# Decoup_Cap_2.net
KiCad netlist of a schematic drawn in Altium Designer
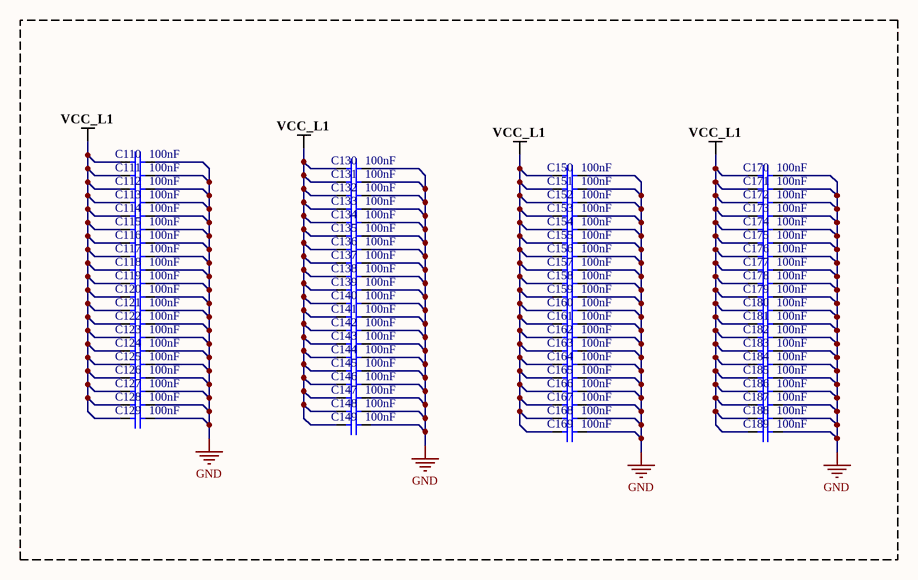
[diagram p0: Decoup_Cap 2.SchDoc]

(export (version "E")
  (design (tool "Eeschema 10.0.6"))
  (components
    (comp (ref "C110")
      (value "100nF")
      (footprint "Cap0402")
      (description "CAP CER 0.1UF 25V X7R 0402")
      (fields
        (field (name "MANUFACTURER") "Yageo")
        (field (name "MANUFACTURER PART NUMBER") "CC0402KRX7R8BB104")
      )
      (libsource (lib "TT_IntLib") (part "CC0402KRX7R8BB104"))
    )
    (comp (ref "C111")
      (value "100nF")
      (footprint "Cap0402")
      (description "CAP CER 0.1UF 25V X7R 0402")
      (fields
        (field (name "MANUFACTURER") "Yageo")
        (field (name "MANUFACTURER PART NUMBER") "CC0402KRX7R8BB104")
      )
      (libsource (lib "TT_IntLib") (part "CC0402KRX7R8BB104"))
    )
    (comp (ref "C112")
      (value "100nF")
      (footprint "Cap0402")
      (description "CAP CER 0.1UF 25V X7R 0402")
      (fields
        (field (name "MANUFACTURER") "Yageo")
        (field (name "MANUFACTURER PART NUMBER") "CC0402KRX7R8BB104")
      )
      (libsource (lib "TT_IntLib") (part "CC0402KRX7R8BB104"))
    )
    (comp (ref "C113")
      (value "100nF")
      (footprint "Cap0402")
      (description "CAP CER 0.1UF 25V X7R 0402")
      (fields
        (field (name "MANUFACTURER") "Yageo")
        (field (name "MANUFACTURER PART NUMBER") "CC0402KRX7R8BB104")
      )
      (libsource (lib "TT_IntLib") (part "CC0402KRX7R8BB104"))
    )
    (comp (ref "C114")
      (value "100nF")
      (footprint "Cap0402")
      (description "CAP CER 0.1UF 25V X7R 0402")
      (fields
        (field (name "MANUFACTURER") "Yageo")
        (field (name "MANUFACTURER PART NUMBER") "CC0402KRX7R8BB104")
      )
      (libsource (lib "TT_IntLib") (part "CC0402KRX7R8BB104"))
    )
    (comp (ref "C115")
      (value "100nF")
      (footprint "Cap0402")
      (description "CAP CER 0.1UF 25V X7R 0402")
      (fields
        (field (name "MANUFACTURER") "Yageo")
        (field (name "MANUFACTURER PART NUMBER") "CC0402KRX7R8BB104")
      )
      (libsource (lib "TT_IntLib") (part "CC0402KRX7R8BB104"))
    )
    (comp (ref "C116")
      (value "100nF")
      (footprint "Cap0402")
      (description "CAP CER 0.1UF 25V X7R 0402")
      (fields
        (field (name "MANUFACTURER") "Yageo")
        (field (name "MANUFACTURER PART NUMBER") "CC0402KRX7R8BB104")
      )
      (libsource (lib "TT_IntLib") (part "CC0402KRX7R8BB104"))
    )
    (comp (ref "C117")
      (value "100nF")
      (footprint "Cap0402")
      (description "CAP CER 0.1UF 25V X7R 0402")
      (fields
        (field (name "MANUFACTURER") "Yageo")
        (field (name "MANUFACTURER PART NUMBER") "CC0402KRX7R8BB104")
      )
      (libsource (lib "TT_IntLib") (part "CC0402KRX7R8BB104"))
    )
    (comp (ref "C118")
      (value "100nF")
      (footprint "Cap0402")
      (description "CAP CER 0.1UF 25V X7R 0402")
      (fields
        (field (name "MANUFACTURER") "Yageo")
        (field (name "MANUFACTURER PART NUMBER") "CC0402KRX7R8BB104")
      )
      (libsource (lib "TT_IntLib") (part "CC0402KRX7R8BB104"))
    )
    (comp (ref "C119")
      (value "100nF")
      (footprint "Cap0402")
      (description "CAP CER 0.1UF 25V X7R 0402")
      (fields
        (field (name "MANUFACTURER") "Yageo")
        (field (name "MANUFACTURER PART NUMBER") "CC0402KRX7R8BB104")
      )
      (libsource (lib "TT_IntLib") (part "CC0402KRX7R8BB104"))
    )
    (comp (ref "C120")
      (value "100nF")
      (footprint "Cap0402")
      (description "CAP CER 0.1UF 25V X7R 0402")
      (fields
        (field (name "MANUFACTURER") "Yageo")
        (field (name "MANUFACTURER PART NUMBER") "CC0402KRX7R8BB104")
      )
      (libsource (lib "TT_IntLib") (part "CC0402KRX7R8BB104"))
    )
    (comp (ref "C121")
      (value "100nF")
      (footprint "Cap0402")
      (description "CAP CER 0.1UF 25V X7R 0402")
      (fields
        (field (name "MANUFACTURER") "Yageo")
        (field (name "MANUFACTURER PART NUMBER") "CC0402KRX7R8BB104")
      )
      (libsource (lib "TT_IntLib") (part "CC0402KRX7R8BB104"))
    )
    (comp (ref "C122")
      (value "100nF")
      (footprint "Cap0402")
      (description "CAP CER 0.1UF 25V X7R 0402")
      (fields
        (field (name "MANUFACTURER") "Yageo")
        (field (name "MANUFACTURER PART NUMBER") "CC0402KRX7R8BB104")
      )
      (libsource (lib "TT_IntLib") (part "CC0402KRX7R8BB104"))
    )
    (comp (ref "C123")
      (value "100nF")
      (footprint "Cap0402")
      (description "CAP CER 0.1UF 25V X7R 0402")
      (fields
        (field (name "MANUFACTURER") "Yageo")
        (field (name "MANUFACTURER PART NUMBER") "CC0402KRX7R8BB104")
      )
      (libsource (lib "TT_IntLib") (part "CC0402KRX7R8BB104"))
    )
    (comp (ref "C124")
      (value "100nF")
      (footprint "Cap0402")
      (description "CAP CER 0.1UF 25V X7R 0402")
      (fields
        (field (name "MANUFACTURER") "Yageo")
        (field (name "MANUFACTURER PART NUMBER") "CC0402KRX7R8BB104")
      )
      (libsource (lib "TT_IntLib") (part "CC0402KRX7R8BB104"))
    )
    (comp (ref "C125")
      (value "100nF")
      (footprint "Cap0402")
      (description "CAP CER 0.1UF 25V X7R 0402")
      (fields
        (field (name "MANUFACTURER") "Yageo")
        (field (name "MANUFACTURER PART NUMBER") "CC0402KRX7R8BB104")
      )
      (libsource (lib "TT_IntLib") (part "CC0402KRX7R8BB104"))
    )
    (comp (ref "C126")
      (value "100nF")
      (footprint "Cap0402")
      (description "CAP CER 0.1UF 25V X7R 0402")
      (fields
        (field (name "MANUFACTURER") "Yageo")
        (field (name "MANUFACTURER PART NUMBER") "CC0402KRX7R8BB104")
      )
      (libsource (lib "TT_IntLib") (part "CC0402KRX7R8BB104"))
    )
    (comp (ref "C127")
      (value "100nF")
      (footprint "Cap0402")
      (description "CAP CER 0.1UF 25V X7R 0402")
      (fields
        (field (name "MANUFACTURER") "Yageo")
        (field (name "MANUFACTURER PART NUMBER") "CC0402KRX7R8BB104")
      )
      (libsource (lib "TT_IntLib") (part "CC0402KRX7R8BB104"))
    )
    (comp (ref "C128")
      (value "100nF")
      (footprint "Cap0402")
      (description "CAP CER 0.1UF 25V X7R 0402")
      (fields
        (field (name "MANUFACTURER") "Yageo")
        (field (name "MANUFACTURER PART NUMBER") "CC0402KRX7R8BB104")
      )
      (libsource (lib "TT_IntLib") (part "CC0402KRX7R8BB104"))
    )
    (comp (ref "C129")
      (value "100nF")
      (footprint "Cap0402")
      (description "CAP CER 0.1UF 25V X7R 0402")
      (fields
        (field (name "MANUFACTURER") "Yageo")
        (field (name "MANUFACTURER PART NUMBER") "CC0402KRX7R8BB104")
      )
      (libsource (lib "TT_IntLib") (part "CC0402KRX7R8BB104"))
    )
    (comp (ref "C130")
      (value "100nF")
      (footprint "Cap0402")
      (description "CAP CER 0.1UF 25V X7R 0402")
      (fields
        (field (name "MANUFACTURER") "Yageo")
        (field (name "MANUFACTURER PART NUMBER") "CC0402KRX7R8BB104")
      )
      (libsource (lib "TT_IntLib") (part "CC0402KRX7R8BB104"))
    )
    (comp (ref "C131")
      (value "100nF")
      (footprint "Cap0402")
      (description "CAP CER 0.1UF 25V X7R 0402")
      (fields
        (field (name "MANUFACTURER") "Yageo")
        (field (name "MANUFACTURER PART NUMBER") "CC0402KRX7R8BB104")
      )
      (libsource (lib "TT_IntLib") (part "CC0402KRX7R8BB104"))
    )
    (comp (ref "C132")
      (value "100nF")
      (footprint "Cap0402")
      (description "CAP CER 0.1UF 25V X7R 0402")
      (fields
        (field (name "MANUFACTURER") "Yageo")
        (field (name "MANUFACTURER PART NUMBER") "CC0402KRX7R8BB104")
      )
      (libsource (lib "TT_IntLib") (part "CC0402KRX7R8BB104"))
    )
    (comp (ref "C133")
      (value "100nF")
      (footprint "Cap0402")
      (description "CAP CER 0.1UF 25V X7R 0402")
      (fields
        (field (name "MANUFACTURER") "Yageo")
        (field (name "MANUFACTURER PART NUMBER") "CC0402KRX7R8BB104")
      )
      (libsource (lib "TT_IntLib") (part "CC0402KRX7R8BB104"))
    )
    (comp (ref "C134")
      (value "100nF")
      (footprint "Cap0402")
      (description "CAP CER 0.1UF 25V X7R 0402")
      (fields
        (field (name "MANUFACTURER") "Yageo")
        (field (name "MANUFACTURER PART NUMBER") "CC0402KRX7R8BB104")
      )
      (libsource (lib "TT_IntLib") (part "CC0402KRX7R8BB104"))
    )
    (comp (ref "C135")
      (value "100nF")
      (footprint "Cap0402")
      (description "CAP CER 0.1UF 25V X7R 0402")
      (fields
        (field (name "MANUFACTURER") "Yageo")
        (field (name "MANUFACTURER PART NUMBER") "CC0402KRX7R8BB104")
      )
      (libsource (lib "TT_IntLib") (part "CC0402KRX7R8BB104"))
    )
    (comp (ref "C136")
      (value "100nF")
      (footprint "Cap0402")
      (description "CAP CER 0.1UF 25V X7R 0402")
      (fields
        (field (name "MANUFACTURER") "Yageo")
        (field (name "MANUFACTURER PART NUMBER") "CC0402KRX7R8BB104")
      )
      (libsource (lib "TT_IntLib") (part "CC0402KRX7R8BB104"))
    )
    (comp (ref "C137")
      (value "100nF")
      (footprint "Cap0402")
      (description "CAP CER 0.1UF 25V X7R 0402")
      (fields
        (field (name "MANUFACTURER") "Yageo")
        (field (name "MANUFACTURER PART NUMBER") "CC0402KRX7R8BB104")
      )
      (libsource (lib "TT_IntLib") (part "CC0402KRX7R8BB104"))
    )
    (comp (ref "C138")
      (value "100nF")
      (footprint "Cap0402")
      (description "CAP CER 0.1UF 25V X7R 0402")
      (fields
        (field (name "MANUFACTURER") "Yageo")
        (field (name "MANUFACTURER PART NUMBER") "CC0402KRX7R8BB104")
      )
      (libsource (lib "TT_IntLib") (part "CC0402KRX7R8BB104"))
    )
    (comp (ref "C139")
      (value "100nF")
      (footprint "Cap0402")
      (description "CAP CER 0.1UF 25V X7R 0402")
      (fields
        (field (name "MANUFACTURER") "Yageo")
        (field (name "MANUFACTURER PART NUMBER") "CC0402KRX7R8BB104")
      )
      (libsource (lib "TT_IntLib") (part "CC0402KRX7R8BB104"))
    )
    (comp (ref "C140")
      (value "100nF")
      (footprint "Cap0402")
      (description "CAP CER 0.1UF 25V X7R 0402")
      (fields
        (field (name "MANUFACTURER") "Yageo")
        (field (name "MANUFACTURER PART NUMBER") "CC0402KRX7R8BB104")
      )
      (libsource (lib "TT_IntLib") (part "CC0402KRX7R8BB104"))
    )
    (comp (ref "C141")
      (value "100nF")
      (footprint "Cap0402")
      (description "CAP CER 0.1UF 25V X7R 0402")
      (fields
        (field (name "MANUFACTURER") "Yageo")
        (field (name "MANUFACTURER PART NUMBER") "CC0402KRX7R8BB104")
      )
      (libsource (lib "TT_IntLib") (part "CC0402KRX7R8BB104"))
    )
    (comp (ref "C142")
      (value "100nF")
      (footprint "Cap0402")
      (description "CAP CER 0.1UF 25V X7R 0402")
      (fields
        (field (name "MANUFACTURER") "Yageo")
        (field (name "MANUFACTURER PART NUMBER") "CC0402KRX7R8BB104")
      )
      (libsource (lib "TT_IntLib") (part "CC0402KRX7R8BB104"))
    )
    (comp (ref "C143")
      (value "100nF")
      (footprint "Cap0402")
      (description "CAP CER 0.1UF 25V X7R 0402")
      (fields
        (field (name "MANUFACTURER") "Yageo")
        (field (name "MANUFACTURER PART NUMBER") "CC0402KRX7R8BB104")
      )
      (libsource (lib "TT_IntLib") (part "CC0402KRX7R8BB104"))
    )
    (comp (ref "C144")
      (value "100nF")
      (footprint "Cap0402")
      (description "CAP CER 0.1UF 25V X7R 0402")
      (fields
        (field (name "MANUFACTURER") "Yageo")
        (field (name "MANUFACTURER PART NUMBER") "CC0402KRX7R8BB104")
      )
      (libsource (lib "TT_IntLib") (part "CC0402KRX7R8BB104"))
    )
    (comp (ref "C145")
      (value "100nF")
      (footprint "Cap0402")
      (description "CAP CER 0.1UF 25V X7R 0402")
      (fields
        (field (name "MANUFACTURER") "Yageo")
        (field (name "MANUFACTURER PART NUMBER") "CC0402KRX7R8BB104")
      )
      (libsource (lib "TT_IntLib") (part "CC0402KRX7R8BB104"))
    )
    (comp (ref "C146")
      (value "100nF")
      (footprint "Cap0402")
      (description "CAP CER 0.1UF 25V X7R 0402")
      (fields
        (field (name "MANUFACTURER") "Yageo")
        (field (name "MANUFACTURER PART NUMBER") "CC0402KRX7R8BB104")
      )
      (libsource (lib "TT_IntLib") (part "CC0402KRX7R8BB104"))
    )
    (comp (ref "C147")
      (value "100nF")
      (footprint "Cap0402")
      (description "CAP CER 0.1UF 25V X7R 0402")
      (fields
        (field (name "MANUFACTURER") "Yageo")
        (field (name "MANUFACTURER PART NUMBER") "CC0402KRX7R8BB104")
      )
      (libsource (lib "TT_IntLib") (part "CC0402KRX7R8BB104"))
    )
    (comp (ref "C148")
      (value "100nF")
      (footprint "Cap0402")
      (description "CAP CER 0.1UF 25V X7R 0402")
      (fields
        (field (name "MANUFACTURER") "Yageo")
        (field (name "MANUFACTURER PART NUMBER") "CC0402KRX7R8BB104")
      )
      (libsource (lib "TT_IntLib") (part "CC0402KRX7R8BB104"))
    )
    (comp (ref "C149")
      (value "100nF")
      (footprint "Cap0402")
      (description "CAP CER 0.1UF 25V X7R 0402")
      (fields
        (field (name "MANUFACTURER") "Yageo")
        (field (name "MANUFACTURER PART NUMBER") "CC0402KRX7R8BB104")
      )
      (libsource (lib "TT_IntLib") (part "CC0402KRX7R8BB104"))
    )
    (comp (ref "C150")
      (value "100nF")
      (footprint "Cap0402")
      (description "CAP CER 0.1UF 25V X7R 0402")
      (fields
        (field (name "MANUFACTURER") "Yageo")
        (field (name "MANUFACTURER PART NUMBER") "CC0402KRX7R8BB104")
      )
      (libsource (lib "TT_IntLib") (part "CC0402KRX7R8BB104"))
    )
    (comp (ref "C151")
      (value "100nF")
      (footprint "Cap0402")
      (description "CAP CER 0.1UF 25V X7R 0402")
      (fields
        (field (name "MANUFACTURER") "Yageo")
        (field (name "MANUFACTURER PART NUMBER") "CC0402KRX7R8BB104")
      )
      (libsource (lib "TT_IntLib") (part "CC0402KRX7R8BB104"))
    )
    (comp (ref "C152")
      (value "100nF")
      (footprint "Cap0402")
      (description "CAP CER 0.1UF 25V X7R 0402")
      (fields
        (field (name "MANUFACTURER") "Yageo")
        (field (name "MANUFACTURER PART NUMBER") "CC0402KRX7R8BB104")
      )
      (libsource (lib "TT_IntLib") (part "CC0402KRX7R8BB104"))
    )
    (comp (ref "C153")
      (value "100nF")
      (footprint "Cap0402")
      (description "CAP CER 0.1UF 25V X7R 0402")
      (fields
        (field (name "MANUFACTURER") "Yageo")
        (field (name "MANUFACTURER PART NUMBER") "CC0402KRX7R8BB104")
      )
      (libsource (lib "TT_IntLib") (part "CC0402KRX7R8BB104"))
    )
    (comp (ref "C154")
      (value "100nF")
      (footprint "Cap0402")
      (description "CAP CER 0.1UF 25V X7R 0402")
      (fields
        (field (name "MANUFACTURER") "Yageo")
        (field (name "MANUFACTURER PART NUMBER") "CC0402KRX7R8BB104")
      )
      (libsource (lib "TT_IntLib") (part "CC0402KRX7R8BB104"))
    )
    (comp (ref "C155")
      (value "100nF")
      (footprint "Cap0402")
      (description "CAP CER 0.1UF 25V X7R 0402")
      (fields
        (field (name "MANUFACTURER") "Yageo")
        (field (name "MANUFACTURER PART NUMBER") "CC0402KRX7R8BB104")
      )
      (libsource (lib "TT_IntLib") (part "CC0402KRX7R8BB104"))
    )
    (comp (ref "C156")
      (value "100nF")
      (footprint "Cap0402")
      (description "CAP CER 0.1UF 25V X7R 0402")
      (fields
        (field (name "MANUFACTURER") "Yageo")
        (field (name "MANUFACTURER PART NUMBER") "CC0402KRX7R8BB104")
      )
      (libsource (lib "TT_IntLib") (part "CC0402KRX7R8BB104"))
    )
    (comp (ref "C157")
      (value "100nF")
      (footprint "Cap0402")
      (description "CAP CER 0.1UF 25V X7R 0402")
      (fields
        (field (name "MANUFACTURER") "Yageo")
        (field (name "MANUFACTURER PART NUMBER") "CC0402KRX7R8BB104")
      )
      (libsource (lib "TT_IntLib") (part "CC0402KRX7R8BB104"))
    )
    (comp (ref "C158")
      (value "100nF")
      (footprint "Cap0402")
      (description "CAP CER 0.1UF 25V X7R 0402")
      (fields
        (field (name "MANUFACTURER") "Yageo")
        (field (name "MANUFACTURER PART NUMBER") "CC0402KRX7R8BB104")
      )
      (libsource (lib "TT_IntLib") (part "CC0402KRX7R8BB104"))
    )
    (comp (ref "C159")
      (value "100nF")
      (footprint "Cap0402")
      (description "CAP CER 0.1UF 25V X7R 0402")
      (fields
        (field (name "MANUFACTURER") "Yageo")
        (field (name "MANUFACTURER PART NUMBER") "CC0402KRX7R8BB104")
      )
      (libsource (lib "TT_IntLib") (part "CC0402KRX7R8BB104"))
    )
    (comp (ref "C160")
      (value "100nF")
      (footprint "Cap0402")
      (description "CAP CER 0.1UF 25V X7R 0402")
      (fields
        (field (name "MANUFACTURER") "Yageo")
        (field (name "MANUFACTURER PART NUMBER") "CC0402KRX7R8BB104")
      )
      (libsource (lib "TT_IntLib") (part "CC0402KRX7R8BB104"))
    )
    (comp (ref "C161")
      (value "100nF")
      (footprint "Cap0402")
      (description "CAP CER 0.1UF 25V X7R 0402")
      (fields
        (field (name "MANUFACTURER") "Yageo")
        (field (name "MANUFACTURER PART NUMBER") "CC0402KRX7R8BB104")
      )
      (libsource (lib "TT_IntLib") (part "CC0402KRX7R8BB104"))
    )
    (comp (ref "C162")
      (value "100nF")
      (footprint "Cap0402")
      (description "CAP CER 0.1UF 25V X7R 0402")
      (fields
        (field (name "MANUFACTURER") "Yageo")
        (field (name "MANUFACTURER PART NUMBER") "CC0402KRX7R8BB104")
      )
      (libsource (lib "TT_IntLib") (part "CC0402KRX7R8BB104"))
    )
    (comp (ref "C163")
      (value "100nF")
      (footprint "Cap0402")
      (description "CAP CER 0.1UF 25V X7R 0402")
      (fields
        (field (name "MANUFACTURER") "Yageo")
        (field (name "MANUFACTURER PART NUMBER") "CC0402KRX7R8BB104")
      )
      (libsource (lib "TT_IntLib") (part "CC0402KRX7R8BB104"))
    )
    (comp (ref "C164")
      (value "100nF")
      (footprint "Cap0402")
      (description "CAP CER 0.1UF 25V X7R 0402")
      (fields
        (field (name "MANUFACTURER") "Yageo")
        (field (name "MANUFACTURER PART NUMBER") "CC0402KRX7R8BB104")
      )
      (libsource (lib "TT_IntLib") (part "CC0402KRX7R8BB104"))
    )
    (comp (ref "C165")
      (value "100nF")
      (footprint "Cap0402")
      (description "CAP CER 0.1UF 25V X7R 0402")
      (fields
        (field (name "MANUFACTURER") "Yageo")
        (field (name "MANUFACTURER PART NUMBER") "CC0402KRX7R8BB104")
      )
      (libsource (lib "TT_IntLib") (part "CC0402KRX7R8BB104"))
    )
    (comp (ref "C166")
      (value "100nF")
      (footprint "Cap0402")
      (description "CAP CER 0.1UF 25V X7R 0402")
      (fields
        (field (name "MANUFACTURER") "Yageo")
        (field (name "MANUFACTURER PART NUMBER") "CC0402KRX7R8BB104")
      )
      (libsource (lib "TT_IntLib") (part "CC0402KRX7R8BB104"))
    )
    (comp (ref "C167")
      (value "100nF")
      (footprint "Cap0402")
      (description "CAP CER 0.1UF 25V X7R 0402")
      (fields
        (field (name "MANUFACTURER") "Yageo")
        (field (name "MANUFACTURER PART NUMBER") "CC0402KRX7R8BB104")
      )
      (libsource (lib "TT_IntLib") (part "CC0402KRX7R8BB104"))
    )
    (comp (ref "C168")
      (value "100nF")
      (footprint "Cap0402")
      (description "CAP CER 0.1UF 25V X7R 0402")
      (fields
        (field (name "MANUFACTURER") "Yageo")
        (field (name "MANUFACTURER PART NUMBER") "CC0402KRX7R8BB104")
      )
      (libsource (lib "TT_IntLib") (part "CC0402KRX7R8BB104"))
    )
    (comp (ref "C169")
      (value "100nF")
      (footprint "Cap0402")
      (description "CAP CER 0.1UF 25V X7R 0402")
      (fields
        (field (name "MANUFACTURER") "Yageo")
        (field (name "MANUFACTURER PART NUMBER") "CC0402KRX7R8BB104")
      )
      (libsource (lib "TT_IntLib") (part "CC0402KRX7R8BB104"))
    )
    (comp (ref "C170")
      (value "100nF")
      (footprint "Cap0402")
      (description "CAP CER 0.1UF 25V X7R 0402")
      (fields
        (field (name "MANUFACTURER") "Yageo")
        (field (name "MANUFACTURER PART NUMBER") "CC0402KRX7R8BB104")
      )
      (libsource (lib "TT_IntLib") (part "CC0402KRX7R8BB104"))
    )
    (comp (ref "C171")
      (value "100nF")
      (footprint "Cap0402")
      (description "CAP CER 0.1UF 25V X7R 0402")
      (fields
        (field (name "MANUFACTURER") "Yageo")
        (field (name "MANUFACTURER PART NUMBER") "CC0402KRX7R8BB104")
      )
      (libsource (lib "TT_IntLib") (part "CC0402KRX7R8BB104"))
    )
    (comp (ref "C172")
      (value "100nF")
      (footprint "Cap0402")
      (description "CAP CER 0.1UF 25V X7R 0402")
      (fields
        (field (name "MANUFACTURER") "Yageo")
        (field (name "MANUFACTURER PART NUMBER") "CC0402KRX7R8BB104")
      )
      (libsource (lib "TT_IntLib") (part "CC0402KRX7R8BB104"))
    )
    (comp (ref "C173")
      (value "100nF")
      (footprint "Cap0402")
      (description "CAP CER 0.1UF 25V X7R 0402")
      (fields
        (field (name "MANUFACTURER") "Yageo")
        (field (name "MANUFACTURER PART NUMBER") "CC0402KRX7R8BB104")
      )
      (libsource (lib "TT_IntLib") (part "CC0402KRX7R8BB104"))
    )
    (comp (ref "C174")
      (value "100nF")
      (footprint "Cap0402")
      (description "CAP CER 0.1UF 25V X7R 0402")
      (fields
        (field (name "MANUFACTURER") "Yageo")
        (field (name "MANUFACTURER PART NUMBER") "CC0402KRX7R8BB104")
      )
      (libsource (lib "TT_IntLib") (part "CC0402KRX7R8BB104"))
    )
    (comp (ref "C175")
      (value "100nF")
      (footprint "Cap0402")
      (description "CAP CER 0.1UF 25V X7R 0402")
      (fields
        (field (name "MANUFACTURER") "Yageo")
        (field (name "MANUFACTURER PART NUMBER") "CC0402KRX7R8BB104")
      )
      (libsource (lib "TT_IntLib") (part "CC0402KRX7R8BB104"))
    )
    (comp (ref "C176")
      (value "100nF")
      (footprint "Cap0402")
      (description "CAP CER 0.1UF 25V X7R 0402")
      (fields
        (field (name "MANUFACTURER") "Yageo")
        (field (name "MANUFACTURER PART NUMBER") "CC0402KRX7R8BB104")
      )
      (libsource (lib "TT_IntLib") (part "CC0402KRX7R8BB104"))
    )
    (comp (ref "C177")
      (value "100nF")
      (footprint "Cap0402")
      (description "CAP CER 0.1UF 25V X7R 0402")
      (fields
        (field (name "MANUFACTURER") "Yageo")
        (field (name "MANUFACTURER PART NUMBER") "CC0402KRX7R8BB104")
      )
      (libsource (lib "TT_IntLib") (part "CC0402KRX7R8BB104"))
    )
    (comp (ref "C178")
      (value "100nF")
      (footprint "Cap0402")
      (description "CAP CER 0.1UF 25V X7R 0402")
      (fields
        (field (name "MANUFACTURER") "Yageo")
        (field (name "MANUFACTURER PART NUMBER") "CC0402KRX7R8BB104")
      )
      (libsource (lib "TT_IntLib") (part "CC0402KRX7R8BB104"))
    )
    (comp (ref "C179")
      (value "100nF")
      (footprint "Cap0402")
      (description "CAP CER 0.1UF 25V X7R 0402")
      (fields
        (field (name "MANUFACTURER") "Yageo")
        (field (name "MANUFACTURER PART NUMBER") "CC0402KRX7R8BB104")
      )
      (libsource (lib "TT_IntLib") (part "CC0402KRX7R8BB104"))
    )
    (comp (ref "C180")
      (value "100nF")
      (footprint "Cap0402")
      (description "CAP CER 0.1UF 25V X7R 0402")
      (fields
        (field (name "MANUFACTURER") "Yageo")
        (field (name "MANUFACTURER PART NUMBER") "CC0402KRX7R8BB104")
      )
      (libsource (lib "TT_IntLib") (part "CC0402KRX7R8BB104"))
    )
    (comp (ref "C181")
      (value "100nF")
      (footprint "Cap0402")
      (description "CAP CER 0.1UF 25V X7R 0402")
      (fields
        (field (name "MANUFACTURER") "Yageo")
        (field (name "MANUFACTURER PART NUMBER") "CC0402KRX7R8BB104")
      )
      (libsource (lib "TT_IntLib") (part "CC0402KRX7R8BB104"))
    )
    (comp (ref "C182")
      (value "100nF")
      (footprint "Cap0402")
      (description "CAP CER 0.1UF 25V X7R 0402")
      (fields
        (field (name "MANUFACTURER") "Yageo")
        (field (name "MANUFACTURER PART NUMBER") "CC0402KRX7R8BB104")
      )
      (libsource (lib "TT_IntLib") (part "CC0402KRX7R8BB104"))
    )
    (comp (ref "C183")
      (value "100nF")
      (footprint "Cap0402")
      (description "CAP CER 0.1UF 25V X7R 0402")
      (fields
        (field (name "MANUFACTURER") "Yageo")
        (field (name "MANUFACTURER PART NUMBER") "CC0402KRX7R8BB104")
      )
      (libsource (lib "TT_IntLib") (part "CC0402KRX7R8BB104"))
    )
    (comp (ref "C184")
      (value "100nF")
      (footprint "Cap0402")
      (description "CAP CER 0.1UF 25V X7R 0402")
      (fields
        (field (name "MANUFACTURER") "Yageo")
        (field (name "MANUFACTURER PART NUMBER") "CC0402KRX7R8BB104")
      )
      (libsource (lib "TT_IntLib") (part "CC0402KRX7R8BB104"))
    )
    (comp (ref "C185")
      (value "100nF")
      (footprint "Cap0402")
      (description "CAP CER 0.1UF 25V X7R 0402")
      (fields
        (field (name "MANUFACTURER") "Yageo")
        (field (name "MANUFACTURER PART NUMBER") "CC0402KRX7R8BB104")
      )
      (libsource (lib "TT_IntLib") (part "CC0402KRX7R8BB104"))
    )
    (comp (ref "C186")
      (value "100nF")
      (footprint "Cap0402")
      (description "CAP CER 0.1UF 25V X7R 0402")
      (fields
        (field (name "MANUFACTURER") "Yageo")
        (field (name "MANUFACTURER PART NUMBER") "CC0402KRX7R8BB104")
      )
      (libsource (lib "TT_IntLib") (part "CC0402KRX7R8BB104"))
    )
    (comp (ref "C187")
      (value "100nF")
      (footprint "Cap0402")
      (description "CAP CER 0.1UF 25V X7R 0402")
      (fields
        (field (name "MANUFACTURER") "Yageo")
        (field (name "MANUFACTURER PART NUMBER") "CC0402KRX7R8BB104")
      )
      (libsource (lib "TT_IntLib") (part "CC0402KRX7R8BB104"))
    )
    (comp (ref "C188")
      (value "100nF")
      (footprint "Cap0402")
      (description "CAP CER 0.1UF 25V X7R 0402")
      (fields
        (field (name "MANUFACTURER") "Yageo")
        (field (name "MANUFACTURER PART NUMBER") "CC0402KRX7R8BB104")
      )
      (libsource (lib "TT_IntLib") (part "CC0402KRX7R8BB104"))
    )
    (comp (ref "C189")
      (value "100nF")
      (footprint "Cap0402")
      (description "CAP CER 0.1UF 25V X7R 0402")
      (fields
        (field (name "MANUFACTURER") "Yageo")
        (field (name "MANUFACTURER PART NUMBER") "CC0402KRX7R8BB104")
      )
      (libsource (lib "TT_IntLib") (part "CC0402KRX7R8BB104"))
    )
  )
  (nets
    (net (code "1") (name "GND") (class "Default")
      (node (ref "C110") (pin "1") (pintype "passive"))
      (node (ref "C111") (pin "1") (pintype "passive"))
      (node (ref "C112") (pin "1") (pintype "passive"))
      (node (ref "C113") (pin "1") (pintype "passive"))
      (node (ref "C114") (pin "1") (pintype "passive"))
      (node (ref "C115") (pin "1") (pintype "passive"))
      (node (ref "C116") (pin "1") (pintype "passive"))
      (node (ref "C117") (pin "1") (pintype "passive"))
      (node (ref "C118") (pin "1") (pintype "passive"))
      (node (ref "C119") (pin "1") (pintype "passive"))
      (node (ref "C120") (pin "1") (pintype "passive"))
      (node (ref "C121") (pin "1") (pintype "passive"))
      (node (ref "C122") (pin "1") (pintype "passive"))
      (node (ref "C123") (pin "1") (pintype "passive"))
      (node (ref "C124") (pin "1") (pintype "passive"))
      (node (ref "C125") (pin "1") (pintype "passive"))
      (node (ref "C126") (pin "1") (pintype "passive"))
      (node (ref "C127") (pin "1") (pintype "passive"))
      (node (ref "C128") (pin "1") (pintype "passive"))
      (node (ref "C129") (pin "1") (pintype "passive"))
      (node (ref "C130") (pin "1") (pintype "passive"))
      (node (ref "C131") (pin "1") (pintype "passive"))
      (node (ref "C132") (pin "1") (pintype "passive"))
      (node (ref "C133") (pin "1") (pintype "passive"))
      (node (ref "C134") (pin "1") (pintype "passive"))
      (node (ref "C135") (pin "1") (pintype "passive"))
      (node (ref "C136") (pin "1") (pintype "passive"))
      (node (ref "C137") (pin "1") (pintype "passive"))
      (node (ref "C138") (pin "1") (pintype "passive"))
      (node (ref "C139") (pin "1") (pintype "passive"))
      (node (ref "C140") (pin "1") (pintype "passive"))
      (node (ref "C141") (pin "1") (pintype "passive"))
      (node (ref "C142") (pin "1") (pintype "passive"))
      (node (ref "C143") (pin "1") (pintype "passive"))
      (node (ref "C144") (pin "1") (pintype "passive"))
      (node (ref "C145") (pin "1") (pintype "passive"))
      (node (ref "C146") (pin "1") (pintype "passive"))
      (node (ref "C147") (pin "1") (pintype "passive"))
      (node (ref "C148") (pin "1") (pintype "passive"))
      (node (ref "C149") (pin "1") (pintype "passive"))
      (node (ref "C150") (pin "1") (pintype "passive"))
      (node (ref "C151") (pin "1") (pintype "passive"))
      (node (ref "C152") (pin "1") (pintype "passive"))
      (node (ref "C153") (pin "1") (pintype "passive"))
      (node (ref "C154") (pin "1") (pintype "passive"))
      (node (ref "C155") (pin "1") (pintype "passive"))
      (node (ref "C156") (pin "1") (pintype "passive"))
      (node (ref "C157") (pin "1") (pintype "passive"))
      (node (ref "C158") (pin "1") (pintype "passive"))
      (node (ref "C159") (pin "1") (pintype "passive"))
      (node (ref "C160") (pin "1") (pintype "passive"))
      (node (ref "C161") (pin "1") (pintype "passive"))
      (node (ref "C162") (pin "1") (pintype "passive"))
      (node (ref "C163") (pin "1") (pintype "passive"))
      (node (ref "C164") (pin "1") (pintype "passive"))
      (node (ref "C165") (pin "1") (pintype "passive"))
      (node (ref "C166") (pin "1") (pintype "passive"))
      (node (ref "C167") (pin "1") (pintype "passive"))
      (node (ref "C168") (pin "1") (pintype "passive"))
      (node (ref "C169") (pin "1") (pintype "passive"))
      (node (ref "C170") (pin "1") (pintype "passive"))
      (node (ref "C171") (pin "1") (pintype "passive"))
      (node (ref "C172") (pin "1") (pintype "passive"))
      (node (ref "C173") (pin "1") (pintype "passive"))
      (node (ref "C174") (pin "1") (pintype "passive"))
      (node (ref "C175") (pin "1") (pintype "passive"))
      (node (ref "C176") (pin "1") (pintype "passive"))
      (node (ref "C177") (pin "1") (pintype "passive"))
      (node (ref "C178") (pin "1") (pintype "passive"))
      (node (ref "C179") (pin "1") (pintype "passive"))
      (node (ref "C180") (pin "1") (pintype "passive"))
      (node (ref "C181") (pin "1") (pintype "passive"))
      (node (ref "C182") (pin "1") (pintype "passive"))
      (node (ref "C183") (pin "1") (pintype "passive"))
      (node (ref "C184") (pin "1") (pintype "passive"))
      (node (ref "C185") (pin "1") (pintype "passive"))
      (node (ref "C186") (pin "1") (pintype "passive"))
      (node (ref "C187") (pin "1") (pintype "passive"))
      (node (ref "C188") (pin "1") (pintype "passive"))
      (node (ref "C189") (pin "1") (pintype "passive"))
    )
    (net (code "2") (name "VCC_L1") (class "Default")
      (node (ref "C110") (pin "2") (pintype "passive"))
      (node (ref "C111") (pin "2") (pintype "passive"))
      (node (ref "C112") (pin "2") (pintype "passive"))
      (node (ref "C113") (pin "2") (pintype "passive"))
      (node (ref "C114") (pin "2") (pintype "passive"))
      (node (ref "C115") (pin "2") (pintype "passive"))
      (node (ref "C116") (pin "2") (pintype "passive"))
      (node (ref "C117") (pin "2") (pintype "passive"))
      (node (ref "C118") (pin "2") (pintype "passive"))
      (node (ref "C119") (pin "2") (pintype "passive"))
      (node (ref "C120") (pin "2") (pintype "passive"))
      (node (ref "C121") (pin "2") (pintype "passive"))
      (node (ref "C122") (pin "2") (pintype "passive"))
      (node (ref "C123") (pin "2") (pintype "passive"))
      (node (ref "C124") (pin "2") (pintype "passive"))
      (node (ref "C125") (pin "2") (pintype "passive"))
      (node (ref "C126") (pin "2") (pintype "passive"))
      (node (ref "C127") (pin "2") (pintype "passive"))
      (node (ref "C128") (pin "2") (pintype "passive"))
      (node (ref "C129") (pin "2") (pintype "passive"))
      (node (ref "C130") (pin "2") (pintype "passive"))
      (node (ref "C131") (pin "2") (pintype "passive"))
      (node (ref "C132") (pin "2") (pintype "passive"))
      (node (ref "C133") (pin "2") (pintype "passive"))
      (node (ref "C134") (pin "2") (pintype "passive"))
      (node (ref "C135") (pin "2") (pintype "passive"))
      (node (ref "C136") (pin "2") (pintype "passive"))
      (node (ref "C137") (pin "2") (pintype "passive"))
      (node (ref "C138") (pin "2") (pintype "passive"))
      (node (ref "C139") (pin "2") (pintype "passive"))
      (node (ref "C140") (pin "2") (pintype "passive"))
      (node (ref "C141") (pin "2") (pintype "passive"))
      (node (ref "C142") (pin "2") (pintype "passive"))
      (node (ref "C143") (pin "2") (pintype "passive"))
      (node (ref "C144") (pin "2") (pintype "passive"))
      (node (ref "C145") (pin "2") (pintype "passive"))
      (node (ref "C146") (pin "2") (pintype "passive"))
      (node (ref "C147") (pin "2") (pintype "passive"))
      (node (ref "C148") (pin "2") (pintype "passive"))
      (node (ref "C149") (pin "2") (pintype "passive"))
      (node (ref "C150") (pin "2") (pintype "passive"))
      (node (ref "C151") (pin "2") (pintype "passive"))
      (node (ref "C152") (pin "2") (pintype "passive"))
      (node (ref "C153") (pin "2") (pintype "passive"))
      (node (ref "C154") (pin "2") (pintype "passive"))
      (node (ref "C155") (pin "2") (pintype "passive"))
      (node (ref "C156") (pin "2") (pintype "passive"))
      (node (ref "C157") (pin "2") (pintype "passive"))
      (node (ref "C158") (pin "2") (pintype "passive"))
      (node (ref "C159") (pin "2") (pintype "passive"))
      (node (ref "C160") (pin "2") (pintype "passive"))
      (node (ref "C161") (pin "2") (pintype "passive"))
      (node (ref "C162") (pin "2") (pintype "passive"))
      (node (ref "C163") (pin "2") (pintype "passive"))
      (node (ref "C164") (pin "2") (pintype "passive"))
      (node (ref "C165") (pin "2") (pintype "passive"))
      (node (ref "C166") (pin "2") (pintype "passive"))
      (node (ref "C167") (pin "2") (pintype "passive"))
      (node (ref "C168") (pin "2") (pintype "passive"))
      (node (ref "C169") (pin "2") (pintype "passive"))
      (node (ref "C170") (pin "2") (pintype "passive"))
      (node (ref "C171") (pin "2") (pintype "passive"))
      (node (ref "C172") (pin "2") (pintype "passive"))
      (node (ref "C173") (pin "2") (pintype "passive"))
      (node (ref "C174") (pin "2") (pintype "passive"))
      (node (ref "C175") (pin "2") (pintype "passive"))
      (node (ref "C176") (pin "2") (pintype "passive"))
      (node (ref "C177") (pin "2") (pintype "passive"))
      (node (ref "C178") (pin "2") (pintype "passive"))
      (node (ref "C179") (pin "2") (pintype "passive"))
      (node (ref "C180") (pin "2") (pintype "passive"))
      (node (ref "C181") (pin "2") (pintype "passive"))
      (node (ref "C182") (pin "2") (pintype "passive"))
      (node (ref "C183") (pin "2") (pintype "passive"))
      (node (ref "C184") (pin "2") (pintype "passive"))
      (node (ref "C185") (pin "2") (pintype "passive"))
      (node (ref "C186") (pin "2") (pintype "passive"))
      (node (ref "C187") (pin "2") (pintype "passive"))
      (node (ref "C188") (pin "2") (pintype "passive"))
      (node (ref "C189") (pin "2") (pintype "passive"))
    )
  )
)
